# dwm.net
KiCad netlist of a schematic drawn in Altium Designer
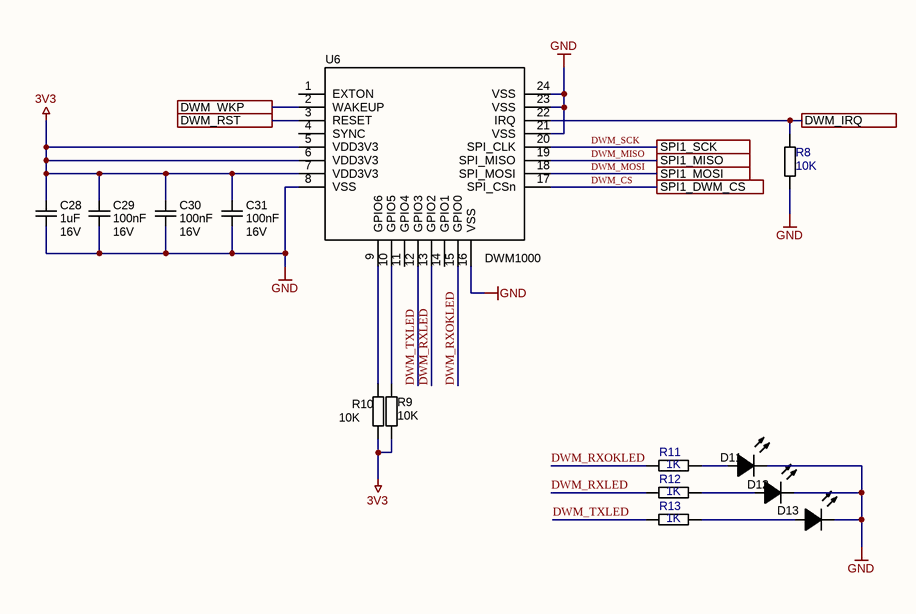
[diagram p0: dwm.SchDoc]

(export (version "E")
  (design (tool "Eeschema 10.0.6"))
  (components
    (comp (ref "C28")
      (value "1uF")
      (footprint "C0603")
      (fields (field (name "VOLTAGE") "16V") (field (name "Comment") "C0603"))
      (libsource (lib "DZ_LIB") (part "C0603"))
    )
    (comp (ref "C29")
      (value "100nF")
      (footprint "C0603")
      (fields (field (name "VOLTAGE") "16V") (field (name "Comment") "C0603"))
      (libsource (lib "DZ_LIB") (part "C0603"))
    )
    (comp (ref "C30")
      (value "100nF")
      (footprint "C0603")
      (fields (field (name "VOLTAGE") "16V") (field (name "Comment") "C0603"))
      (libsource (lib "DZ_LIB") (part "C0603"))
    )
    (comp (ref "C31")
      (value "100nF")
      (footprint "C0603")
      (fields (field (name "VOLTAGE") "16V") (field (name "Comment") "C0603"))
      (libsource (lib "DZ_LIB") (part "C0603"))
    )
    (comp (ref "D11")
      (value "LED0805")
      (footprint "LED0805")
      (description "LED SMD 0805 K1A2")
      (libsource (lib "DZ_LIB") (part "LED0805"))
    )
    (comp (ref "D12")
      (value "LED0805")
      (footprint "LED0805")
      (description "LED SMD 0805 K1A2")
      (libsource (lib "DZ_LIB") (part "LED0805"))
    )
    (comp (ref "D13")
      (value "LED0805")
      (footprint "LED0805")
      (description "LED SMD 0805 K1A2")
      (libsource (lib "DZ_LIB") (part "LED0805"))
    )
    (comp (ref "R8") (value "10K") (footprint "SMD0603") (libsource (lib "") (part "R0603_2")))
    (comp (ref "R9")
      (value "10K")
      (footprint "SMD0603")
      (fields (field (name "Comment") "R0603"))
      (libsource (lib "") (part "R0603_1"))
    )
    (comp (ref "R10")
      (value "10K")
      (footprint "SMD0603")
      (fields (field (name "Comment") "R0603"))
      (libsource (lib "") (part "R0603_1"))
    )
    (comp (ref "R11") (value "1K") (footprint "SMD0603") (libsource (lib "DZ_LIB") (part "R0603")))
    (comp (ref "R12") (value "1K") (footprint "SMD0603") (libsource (lib "DZ_LIB") (part "R0603")))
    (comp (ref "R13") (value "1K") (footprint "SMD0603") (libsource (lib "DZ_LIB") (part "R0603")))
    (comp (ref "U6")
      (value "DWM1000")
      (footprint "DWM1000")
      (description "MOD IEEE802.15.4-2011 UWB TXRX")
      (fields (field (name "MANUFACTURER") "Decawave Limited"))
      (libsource (lib "DZ_LIB") (part "DWM1000"))
    )
  )
  (nets
    (net (code "1") (name "/DWM_CS") (class "Default")
      (node (ref "U6") (pin "17") (pinfunction "SPI_CSn_17") (pintype "passive"))
    )
    (net (code "2") (name "/DWM_IRQ") (class "Default")
      (node (ref "R8") (pin "2") (pinfunction "2_2") (pintype "passive"))
      (node (ref "U6") (pin "22") (pinfunction "IRQ_22") (pintype "passive"))
    )
    (net (code "3") (name "/DWM_MISO") (class "Default")
      (node (ref "U6") (pin "19") (pinfunction "SPI_MISO_19") (pintype "passive"))
    )
    (net (code "4") (name "/DWM_MOSI") (class "Default")
      (node (ref "U6") (pin "18") (pinfunction "SPI_MOSI_18") (pintype "passive"))
    )
    (net (code "5") (name "/DWM_RST") (class "Default")
      (node (ref "U6") (pin "3") (pinfunction "RESET_3") (pintype "passive"))
    )
    (net (code "6") (name "/DWM_RXLED") (class "Default")
      (node (ref "R12") (pin "2") (pinfunction "2_2") (pintype "passive"))
      (node (ref "U6") (pin "13") (pinfunction "GPIO2_13") (pintype "passive"))
    )
    (net (code "7") (name "/DWM_RXOKLED") (class "Default")
      (node (ref "R11") (pin "2") (pinfunction "2_2") (pintype "passive"))
      (node (ref "U6") (pin "15") (pinfunction "GPIO0_15") (pintype "passive"))
    )
    (net (code "8") (name "/DWM_SCK") (class "Default")
      (node (ref "U6") (pin "20") (pinfunction "SPI_CLK_20") (pintype "passive"))
    )
    (net (code "9") (name "/DWM_TXLED") (class "Default")
      (node (ref "R13") (pin "2") (pinfunction "2_2") (pintype "passive"))
      (node (ref "U6") (pin "12") (pinfunction "GPIO3_12") (pintype "passive"))
    )
    (net (code "10") (name "/DWM_WKP") (class "Default")
      (node (ref "U6") (pin "2") (pinfunction "WAKEUP_2") (pintype "passive"))
    )
    (net (code "11") (name "3V3") (class "Default")
      (node (ref "C28") (pin "1") (pinfunction "1_1") (pintype "passive"))
      (node (ref "C29") (pin "1") (pinfunction "1_1") (pintype "passive"))
      (node (ref "C30") (pin "1") (pinfunction "1_1") (pintype "passive"))
      (node (ref "C31") (pin "1") (pinfunction "1_1") (pintype "passive"))
      (node (ref "R10") (pin "2") (pinfunction "2_2") (pintype "passive"))
      (node (ref "R9") (pin "2") (pinfunction "2_2") (pintype "passive"))
      (node (ref "U6") (pin "5") (pinfunction "VDD3V3_5") (pintype "passive"))
      (node (ref "U6") (pin "6") (pinfunction "VDD3V3_6") (pintype "passive"))
      (node (ref "U6") (pin "7") (pinfunction "VDD3V3_7") (pintype "passive"))
    )
    (net (code "12") (name "GND") (class "Default")
      (node (ref "C28") (pin "2") (pinfunction "2_2") (pintype "passive"))
      (node (ref "C29") (pin "2") (pinfunction "2_2") (pintype "passive"))
      (node (ref "C30") (pin "2") (pinfunction "2_2") (pintype "passive"))
      (node (ref "C31") (pin "2") (pinfunction "2_2") (pintype "passive"))
      (node (ref "D11") (pin "1") (pinfunction "K_1") (pintype "passive"))
      (node (ref "D12") (pin "1") (pinfunction "K_1") (pintype "passive"))
      (node (ref "D13") (pin "1") (pinfunction "K_1") (pintype "passive"))
      (node (ref "R8") (pin "1") (pinfunction "1_1") (pintype "passive"))
      (node (ref "U6") (pin "16") (pinfunction "VSS_16") (pintype "passive"))
      (node (ref "U6") (pin "21") (pinfunction "VSS_21") (pintype "passive"))
      (node (ref "U6") (pin "23") (pinfunction "VSS_23") (pintype "passive"))
      (node (ref "U6") (pin "24") (pinfunction "VSS_24") (pintype "passive"))
      (node (ref "U6") (pin "8") (pinfunction "VSS_8") (pintype "passive"))
    )
    (net (code "13") (name "Net-(D11-A)") (class "Default")
      (node (ref "D11") (pin "2") (pinfunction "A_2") (pintype "passive"))
      (node (ref "R11") (pin "1") (pinfunction "1_1") (pintype "passive"))
    )
    (net (code "14") (name "Net-(D12-A)") (class "Default")
      (node (ref "D12") (pin "2") (pinfunction "A_2") (pintype "passive"))
      (node (ref "R12") (pin "1") (pinfunction "1_1") (pintype "passive"))
    )
    (net (code "15") (name "Net-(D13-A)") (class "Default")
      (node (ref "D13") (pin "2") (pinfunction "A_2") (pintype "passive"))
      (node (ref "R13") (pin "1") (pinfunction "1_1") (pintype "passive"))
    )
    (net (code "16") (name "Net-(U6-GPIO5)") (class "Default")
      (node (ref "R9") (pin "1") (pinfunction "1_1") (pintype "passive"))
      (node (ref "U6") (pin "10") (pinfunction "GPIO5_10") (pintype "passive"))
    )
    (net (code "17") (name "Net-(U6-GPIO6)") (class "Default")
      (node (ref "R10") (pin "1") (pinfunction "1_1") (pintype "passive"))
      (node (ref "U6") (pin "9") (pinfunction "GPIO6_9") (pintype "passive"))
    )
    (net (code "18") (name "unconnected-(U6-EXTON-Pad1)") (class "Default")
      (node (ref "U6") (pin "1") (pinfunction "EXTON_1") (pintype "passive"))
    )
    (net (code "19") (name "unconnected-(U6-GPIO1-Pad14)") (class "Default")
      (node (ref "U6") (pin "14") (pinfunction "GPIO1_14") (pintype "passive"))
    )
    (net (code "20") (name "unconnected-(U6-GPIO4-Pad11)") (class "Default")
      (node (ref "U6") (pin "11") (pinfunction "GPIO4_11") (pintype "passive"))
    )
    (net (code "21") (name "unconnected-(U6-SYNC-Pad4)") (class "Default")
      (node (ref "U6") (pin "4") (pinfunction "SYNC_4") (pintype "passive"))
    )
  )
)
